# REDRIVERS.net
KiCad netlist of a schematic drawn in Altium Designer
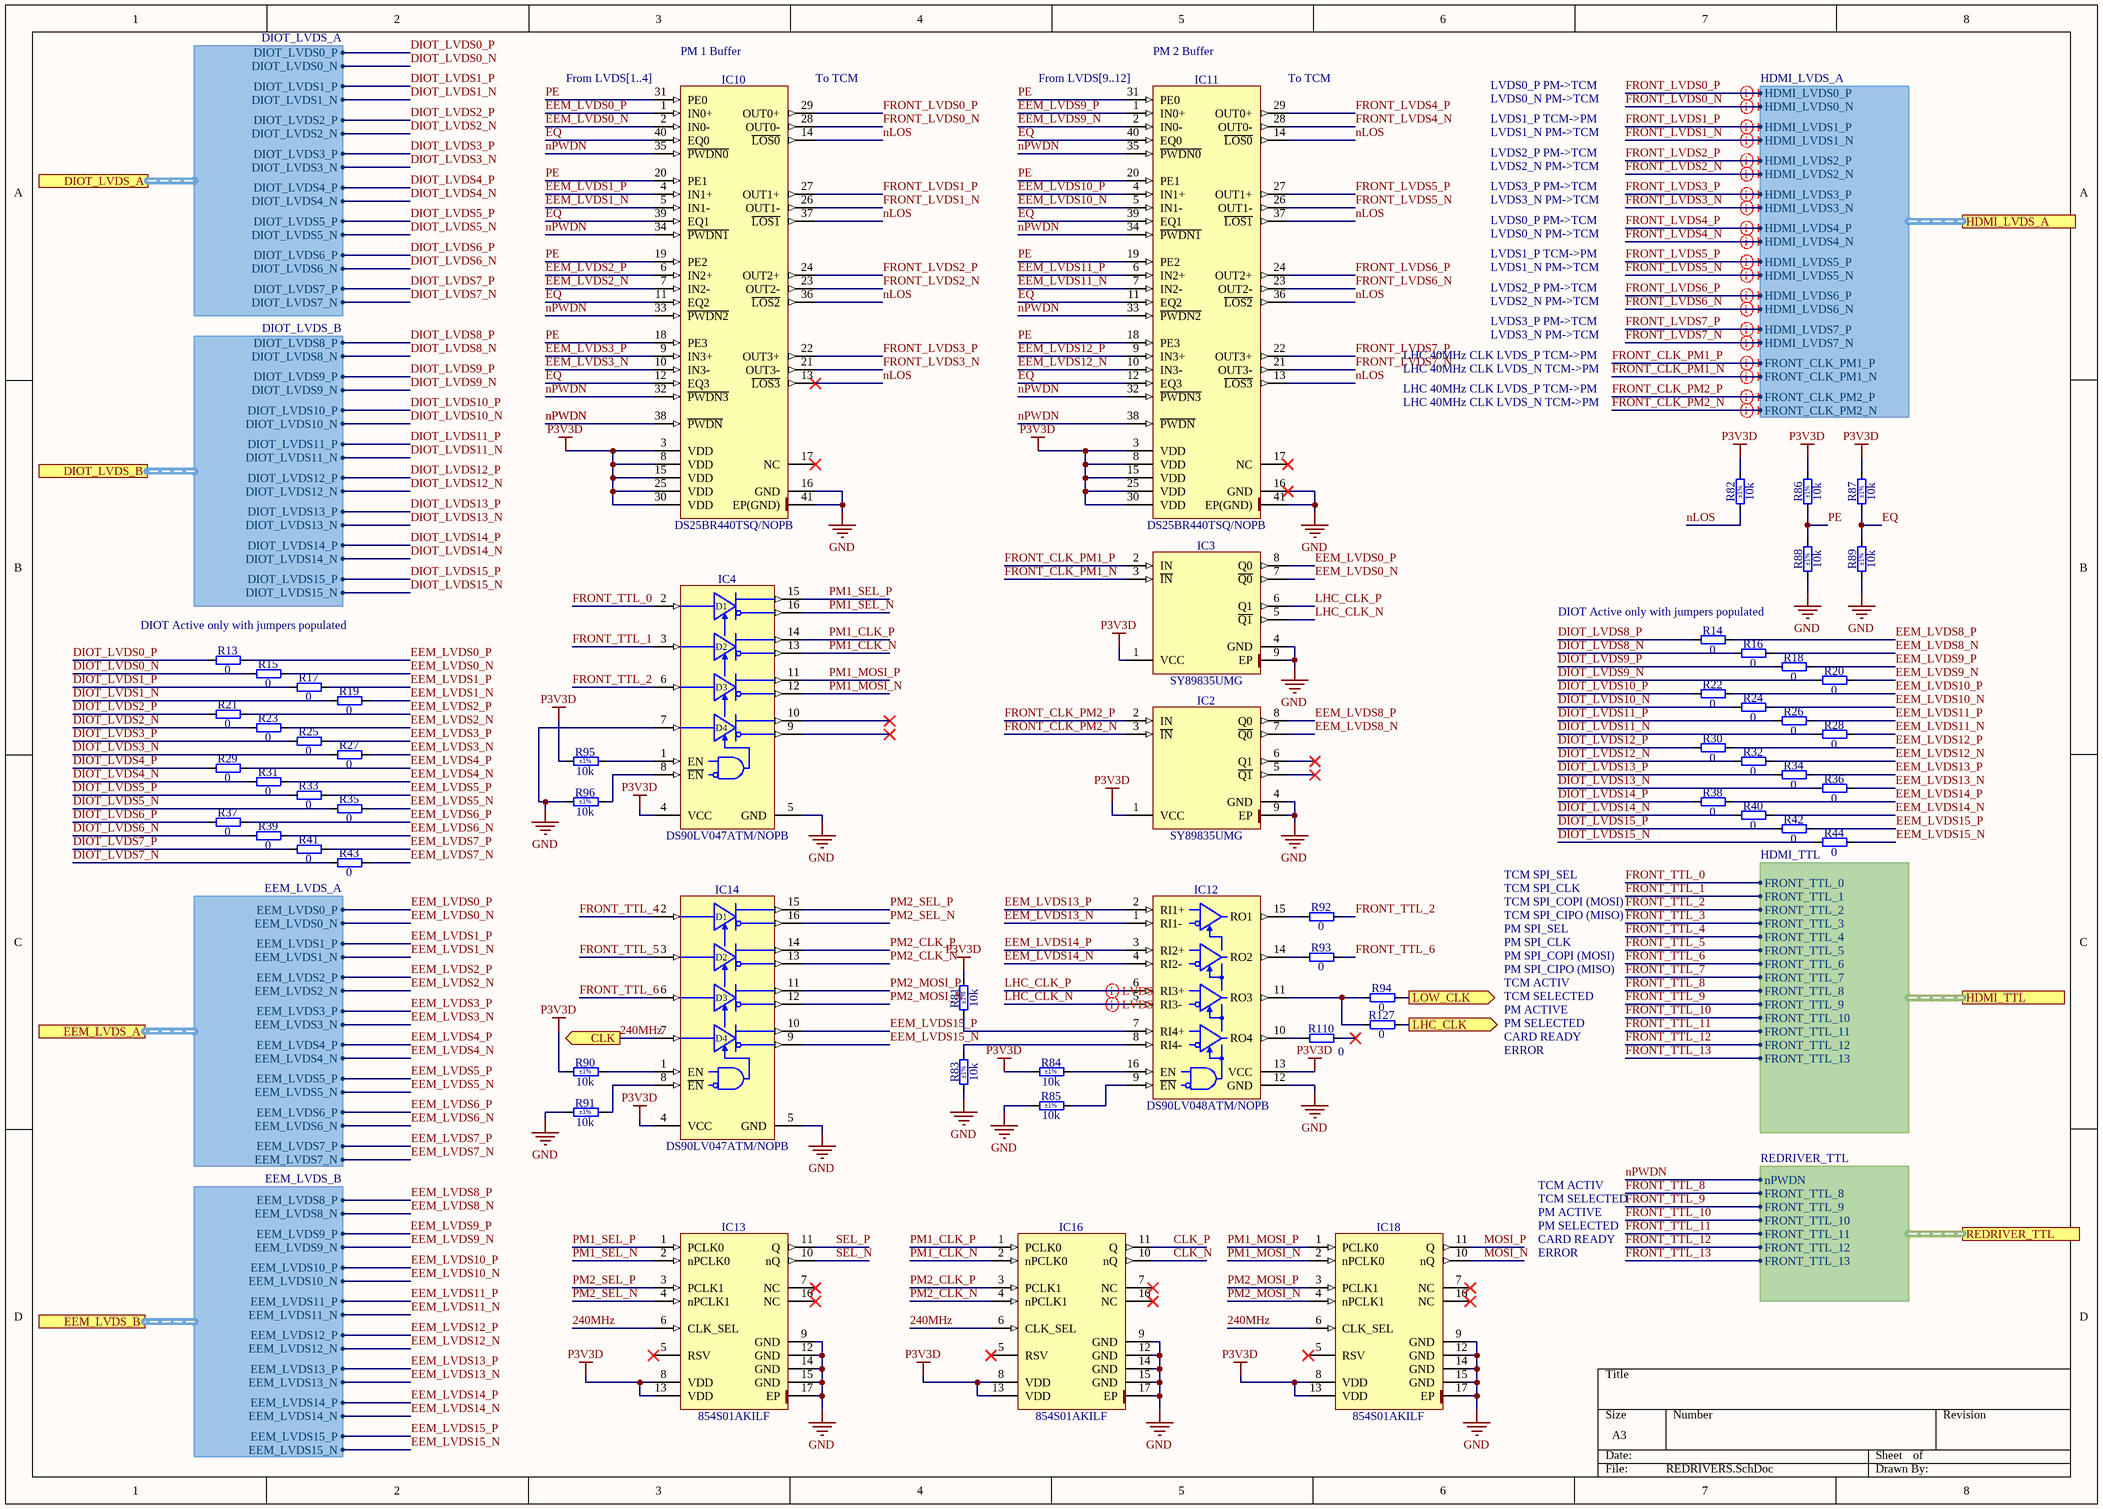
[diagram p0: REDRIVERS.SchDoc]

(export (version "E")
  (design (tool "Eeschema 10.0.6"))
  (components
    (comp (ref "IC2")
      (value "SY89835UMG")
      (footprint "SON50P200X200X90-9N-R70X130")
      (fields (field (name "MANUFACTURER") "MICREL") (field (name "AUTHOR") "CERN DEM MR"))
      (libsource (lib "ICs And Semiconductors") (part "SY89835U"))
    )
    (comp (ref "IC3")
      (value "SY89835UMG")
      (footprint "SON50P200X200X90-9N-R70X130")
      (fields (field (name "MANUFACTURER") "MICREL") (field (name "AUTHOR") "CERN DEM MR"))
      (libsource (lib "ICs And Semiconductors") (part "SY89835U"))
    )
    (comp (ref "IC4")
      (value "DS90LV047ATM/NOPB")
      (footprint "SOIC127P600X175-16N")
      (description "3V LVDS Quad CMOS Differential Line Driver")
      (fields
        (field (name "MANUFACTURER") "TEXAS INSTRUMENTS")
        (field (name "MANUFACTURER PART NUMBER") "DS90LV047ATM")
        (field (name "AUTHOR") "CERN DEM JLC")
      )
      (libsource (lib "ICs And Semiconductors") (part "DS90LV047A"))
    )
    (comp (ref "IC10")
      (value "DS25BR440TSQ/NOPB")
      (footprint "QFN50P600X600X80-41N-S480")
      (description "3.125-Gbps Quad LVDS Buffer with Transmit Pre-Emphasis and Receive Equalization")
      (fields
        (field (name "MANUFACTURER") "TEXAS INSTRUMENTS")
        (field (name "MANUFACTURER PART NUMBER") "DS25BR440TSQ")
        (field (name "AUTHOR") "CERN DEM HF")
      )
      (libsource (lib "ICs And Semiconductors") (part "DS25BR440"))
    )
    (comp (ref "IC11")
      (value "DS25BR440TSQ/NOPB")
      (footprint "QFN50P600X600X80-41N-S480")
      (description "3.125-Gbps Quad LVDS Buffer with Transmit Pre-Emphasis and Receive Equalization")
      (fields
        (field (name "MANUFACTURER") "TEXAS INSTRUMENTS")
        (field (name "MANUFACTURER PART NUMBER") "DS25BR440TSQ")
        (field (name "AUTHOR") "CERN DEM HF")
      )
      (libsource (lib "ICs And Semiconductors") (part "DS25BR440"))
    )
    (comp (ref "IC12")
      (value "DS90LV048ATM/NOPB")
      (footprint "SOIC127P600X175-16N")
      (description "3V LVDS Quad CMOS Differential Line Receiver")
      (fields
        (field (name "MANUFACTURER") "TEXAS INSTRUMENTS")
        (field (name "MANUFACTURER PART NUMBER") "DS90LV048ATM")
        (field (name "AUTHOR") "CERN DEM JLC")
      )
      (libsource (lib "ICs And Semiconductors") (part "DS90LV048A"))
    )
    (comp (ref "IC13")
      (value "854S01AKILF")
      (footprint "QFN50P300X300X100-17N-S180")
      (description "2:1 Differential-to-LVDS Multiplexer")
      (fields
        (field (name "MANUFACTURER") "INTEGRATED DEVICE TECHNOLOGY (IDT)")
        (field (name "AUTHOR") "CERN DEM JLC")
      )
      (libsource (lib "ICs And Semiconductors") (part "854S01AKILF"))
    )
    (comp (ref "IC14")
      (value "DS90LV047ATM/NOPB")
      (footprint "SOIC127P600X175-16N")
      (description "3V LVDS Quad CMOS Differential Line Driver")
      (fields
        (field (name "MANUFACTURER") "TEXAS INSTRUMENTS")
        (field (name "MANUFACTURER PART NUMBER") "DS90LV047ATM")
        (field (name "AUTHOR") "CERN DEM JLC")
      )
      (libsource (lib "ICs And Semiconductors") (part "DS90LV047A"))
    )
    (comp (ref "IC16")
      (value "854S01AKILF")
      (footprint "QFN50P300X300X100-17N-S180")
      (description "2:1 Differential-to-LVDS Multiplexer")
      (fields
        (field (name "MANUFACTURER") "INTEGRATED DEVICE TECHNOLOGY (IDT)")
        (field (name "AUTHOR") "CERN DEM JLC")
      )
      (libsource (lib "ICs And Semiconductors") (part "854S01AKILF"))
    )
    (comp (ref "IC18")
      (value "854S01AKILF")
      (footprint "QFN50P300X300X100-17N-S180")
      (description "2:1 Differential-to-LVDS Multiplexer")
      (fields
        (field (name "MANUFACTURER") "INTEGRATED DEVICE TECHNOLOGY (IDT)")
        (field (name "AUTHOR") "CERN DEM JLC")
      )
      (libsource (lib "ICs And Semiconductors") (part "854S01AKILF"))
    )
    (comp (ref "R13")
      (value "0")
      (footprint "RESC1005X40N")
      (description "Resistor")
      (fields
        (field (name "PART NUMBER") "R0402_0R_JUMPER")
        (field (name "MANUFACTURER") "GENERIC")
        (field (name "AUTHOR") "CERN DEM JLC")
      )
      (libsource (lib "Resistors") (part "Resistor"))
    )
    (comp (ref "R14")
      (value "0")
      (footprint "RESC1005X40N")
      (description "Resistor")
      (fields
        (field (name "PART NUMBER") "R0402_0R_JUMPER")
        (field (name "MANUFACTURER") "GENERIC")
        (field (name "AUTHOR") "CERN DEM JLC")
      )
      (libsource (lib "Resistors") (part "Resistor"))
    )
    (comp (ref "R15")
      (value "0")
      (footprint "RESC1005X40N")
      (description "Resistor")
      (fields
        (field (name "PART NUMBER") "R0402_0R_JUMPER")
        (field (name "MANUFACTURER") "GENERIC")
        (field (name "AUTHOR") "CERN DEM JLC")
      )
      (libsource (lib "Resistors") (part "Resistor"))
    )
    (comp (ref "R16")
      (value "0")
      (footprint "RESC1005X40N")
      (description "Resistor")
      (fields
        (field (name "PART NUMBER") "R0402_0R_JUMPER")
        (field (name "MANUFACTURER") "GENERIC")
        (field (name "AUTHOR") "CERN DEM JLC")
      )
      (libsource (lib "Resistors") (part "Resistor"))
    )
    (comp (ref "R17")
      (value "0")
      (footprint "RESC1005X40N")
      (description "Resistor")
      (fields
        (field (name "PART NUMBER") "R0402_0R_JUMPER")
        (field (name "MANUFACTURER") "GENERIC")
        (field (name "AUTHOR") "CERN DEM JLC")
      )
      (libsource (lib "Resistors") (part "Resistor"))
    )
    (comp (ref "R18")
      (value "0")
      (footprint "RESC1005X40N")
      (description "Resistor")
      (fields
        (field (name "PART NUMBER") "R0402_0R_JUMPER")
        (field (name "MANUFACTURER") "GENERIC")
        (field (name "AUTHOR") "CERN DEM JLC")
      )
      (libsource (lib "Resistors") (part "Resistor"))
    )
    (comp (ref "R19")
      (value "0")
      (footprint "RESC1005X40N")
      (description "Resistor")
      (fields
        (field (name "PART NUMBER") "R0402_0R_JUMPER")
        (field (name "MANUFACTURER") "GENERIC")
        (field (name "AUTHOR") "CERN DEM JLC")
      )
      (libsource (lib "Resistors") (part "Resistor"))
    )
    (comp (ref "R20")
      (value "0")
      (footprint "RESC1005X40N")
      (description "Resistor")
      (fields
        (field (name "PART NUMBER") "R0402_0R_JUMPER")
        (field (name "MANUFACTURER") "GENERIC")
        (field (name "AUTHOR") "CERN DEM JLC")
      )
      (libsource (lib "Resistors") (part "Resistor"))
    )
    (comp (ref "R21")
      (value "0")
      (footprint "RESC1005X40N")
      (description "Resistor")
      (fields
        (field (name "PART NUMBER") "R0402_0R_JUMPER")
        (field (name "MANUFACTURER") "GENERIC")
        (field (name "AUTHOR") "CERN DEM JLC")
      )
      (libsource (lib "Resistors") (part "Resistor"))
    )
    (comp (ref "R22")
      (value "0")
      (footprint "RESC1005X40N")
      (description "Resistor")
      (fields
        (field (name "PART NUMBER") "R0402_0R_JUMPER")
        (field (name "MANUFACTURER") "GENERIC")
        (field (name "AUTHOR") "CERN DEM JLC")
      )
      (libsource (lib "Resistors") (part "Resistor"))
    )
    (comp (ref "R23")
      (value "0")
      (footprint "RESC1005X40N")
      (description "Resistor")
      (fields
        (field (name "PART NUMBER") "R0402_0R_JUMPER")
        (field (name "MANUFACTURER") "GENERIC")
        (field (name "AUTHOR") "CERN DEM JLC")
      )
      (libsource (lib "Resistors") (part "Resistor"))
    )
    (comp (ref "R24")
      (value "0")
      (footprint "RESC1005X40N")
      (description "Resistor")
      (fields
        (field (name "PART NUMBER") "R0402_0R_JUMPER")
        (field (name "MANUFACTURER") "GENERIC")
        (field (name "AUTHOR") "CERN DEM JLC")
      )
      (libsource (lib "Resistors") (part "Resistor"))
    )
    (comp (ref "R25")
      (value "0")
      (footprint "RESC1005X40N")
      (description "Resistor")
      (fields
        (field (name "PART NUMBER") "R0402_0R_JUMPER")
        (field (name "MANUFACTURER") "GENERIC")
        (field (name "AUTHOR") "CERN DEM JLC")
      )
      (libsource (lib "Resistors") (part "Resistor"))
    )
    (comp (ref "R26")
      (value "0")
      (footprint "RESC1005X40N")
      (description "Resistor")
      (fields
        (field (name "PART NUMBER") "R0402_0R_JUMPER")
        (field (name "MANUFACTURER") "GENERIC")
        (field (name "AUTHOR") "CERN DEM JLC")
      )
      (libsource (lib "Resistors") (part "Resistor"))
    )
    (comp (ref "R27")
      (value "0")
      (footprint "RESC1005X40N")
      (description "Resistor")
      (fields
        (field (name "PART NUMBER") "R0402_0R_JUMPER")
        (field (name "MANUFACTURER") "GENERIC")
        (field (name "AUTHOR") "CERN DEM JLC")
      )
      (libsource (lib "Resistors") (part "Resistor"))
    )
    (comp (ref "R28")
      (value "0")
      (footprint "RESC1005X40N")
      (description "Resistor")
      (fields
        (field (name "PART NUMBER") "R0402_0R_JUMPER")
        (field (name "MANUFACTURER") "GENERIC")
        (field (name "AUTHOR") "CERN DEM JLC")
      )
      (libsource (lib "Resistors") (part "Resistor"))
    )
    (comp (ref "R29")
      (value "0")
      (footprint "RESC1005X40N")
      (description "Resistor")
      (fields
        (field (name "PART NUMBER") "R0402_0R_JUMPER")
        (field (name "MANUFACTURER") "GENERIC")
        (field (name "AUTHOR") "CERN DEM JLC")
      )
      (libsource (lib "Resistors") (part "Resistor"))
    )
    (comp (ref "R30")
      (value "0")
      (footprint "RESC1005X40N")
      (description "Resistor")
      (fields
        (field (name "PART NUMBER") "R0402_0R_JUMPER")
        (field (name "MANUFACTURER") "GENERIC")
        (field (name "AUTHOR") "CERN DEM JLC")
      )
      (libsource (lib "Resistors") (part "Resistor"))
    )
    (comp (ref "R31")
      (value "0")
      (footprint "RESC1005X40N")
      (description "Resistor")
      (fields
        (field (name "PART NUMBER") "R0402_0R_JUMPER")
        (field (name "MANUFACTURER") "GENERIC")
        (field (name "AUTHOR") "CERN DEM JLC")
      )
      (libsource (lib "Resistors") (part "Resistor"))
    )
    (comp (ref "R32")
      (value "0")
      (footprint "RESC1005X40N")
      (description "Resistor")
      (fields
        (field (name "PART NUMBER") "R0402_0R_JUMPER")
        (field (name "MANUFACTURER") "GENERIC")
        (field (name "AUTHOR") "CERN DEM JLC")
      )
      (libsource (lib "Resistors") (part "Resistor"))
    )
    (comp (ref "R33")
      (value "0")
      (footprint "RESC1005X40N")
      (description "Resistor")
      (fields
        (field (name "PART NUMBER") "R0402_0R_JUMPER")
        (field (name "MANUFACTURER") "GENERIC")
        (field (name "AUTHOR") "CERN DEM JLC")
      )
      (libsource (lib "Resistors") (part "Resistor"))
    )
    (comp (ref "R34")
      (value "0")
      (footprint "RESC1005X40N")
      (description "Resistor")
      (fields
        (field (name "PART NUMBER") "R0402_0R_JUMPER")
        (field (name "MANUFACTURER") "GENERIC")
        (field (name "AUTHOR") "CERN DEM JLC")
      )
      (libsource (lib "Resistors") (part "Resistor"))
    )
    (comp (ref "R35")
      (value "0")
      (footprint "RESC1005X40N")
      (description "Resistor")
      (fields
        (field (name "PART NUMBER") "R0402_0R_JUMPER")
        (field (name "MANUFACTURER") "GENERIC")
        (field (name "AUTHOR") "CERN DEM JLC")
      )
      (libsource (lib "Resistors") (part "Resistor"))
    )
    (comp (ref "R36")
      (value "0")
      (footprint "RESC1005X40N")
      (description "Resistor")
      (fields
        (field (name "PART NUMBER") "R0402_0R_JUMPER")
        (field (name "MANUFACTURER") "GENERIC")
        (field (name "AUTHOR") "CERN DEM JLC")
      )
      (libsource (lib "Resistors") (part "Resistor"))
    )
    (comp (ref "R37")
      (value "0")
      (footprint "RESC1005X40N")
      (description "Resistor")
      (fields
        (field (name "PART NUMBER") "R0402_0R_JUMPER")
        (field (name "MANUFACTURER") "GENERIC")
        (field (name "AUTHOR") "CERN DEM JLC")
      )
      (libsource (lib "Resistors") (part "Resistor"))
    )
    (comp (ref "R38")
      (value "0")
      (footprint "RESC1005X40N")
      (description "Resistor")
      (fields
        (field (name "PART NUMBER") "R0402_0R_JUMPER")
        (field (name "MANUFACTURER") "GENERIC")
        (field (name "AUTHOR") "CERN DEM JLC")
      )
      (libsource (lib "Resistors") (part "Resistor"))
    )
    (comp (ref "R39")
      (value "0")
      (footprint "RESC1005X40N")
      (description "Resistor")
      (fields
        (field (name "PART NUMBER") "R0402_0R_JUMPER")
        (field (name "MANUFACTURER") "GENERIC")
        (field (name "AUTHOR") "CERN DEM JLC")
      )
      (libsource (lib "Resistors") (part "Resistor"))
    )
    (comp (ref "R40")
      (value "0")
      (footprint "RESC1005X40N")
      (description "Resistor")
      (fields
        (field (name "PART NUMBER") "R0402_0R_JUMPER")
        (field (name "MANUFACTURER") "GENERIC")
        (field (name "AUTHOR") "CERN DEM JLC")
      )
      (libsource (lib "Resistors") (part "Resistor"))
    )
    (comp (ref "R41")
      (value "0")
      (footprint "RESC1005X40N")
      (description "Resistor")
      (fields
        (field (name "PART NUMBER") "R0402_0R_JUMPER")
        (field (name "MANUFACTURER") "GENERIC")
        (field (name "AUTHOR") "CERN DEM JLC")
      )
      (libsource (lib "Resistors") (part "Resistor"))
    )
    (comp (ref "R42")
      (value "0")
      (footprint "RESC1005X40N")
      (description "Resistor")
      (fields
        (field (name "PART NUMBER") "R0402_0R_JUMPER")
        (field (name "MANUFACTURER") "GENERIC")
        (field (name "AUTHOR") "CERN DEM JLC")
      )
      (libsource (lib "Resistors") (part "Resistor"))
    )
    (comp (ref "R43")
      (value "0")
      (footprint "RESC1005X40N")
      (description "Resistor")
      (fields
        (field (name "PART NUMBER") "R0402_0R_JUMPER")
        (field (name "MANUFACTURER") "GENERIC")
        (field (name "AUTHOR") "CERN DEM JLC")
      )
      (libsource (lib "Resistors") (part "Resistor"))
    )
    (comp (ref "R44")
      (value "0")
      (footprint "RESC1005X40N")
      (description "Resistor")
      (fields
        (field (name "PART NUMBER") "R0402_0R_JUMPER")
        (field (name "MANUFACTURER") "GENERIC")
        (field (name "AUTHOR") "CERN DEM JLC")
      )
      (libsource (lib "Resistors") (part "Resistor"))
    )
    (comp (ref "R81")
      (value "10k")
      (footprint "RESC1608X55N")
      (description "Resistor - 1%")
      (fields
        (field (name "TOLERANCE") "±1%")
        (field (name "PART NUMBER") "R0603_10K_1%_0.1W_100PPM")
        (field (name "POWER") "0.1W")
        (field (name "AUTHOR") "CERN DEM JLC")
      )
      (libsource (lib "Resistors") (part "Resistor - 1%"))
    )
    (comp (ref "R82")
      (value "10k")
      (footprint "RESC1608X55N")
      (description "Resistor - 1%")
      (fields
        (field (name "TOLERANCE") "±1%")
        (field (name "PART NUMBER") "R0603_10K_1%_0.1W_100PPM")
        (field (name "POWER") "0.1W")
        (field (name "AUTHOR") "CERN DEM JLC")
      )
      (libsource (lib "Resistors") (part "Resistor - 1%"))
    )
    (comp (ref "R83")
      (value "10k")
      (footprint "RESC1608X55N")
      (description "Resistor - 1%")
      (fields
        (field (name "TOLERANCE") "±1%")
        (field (name "PART NUMBER") "R0603_10K_1%_0.1W_100PPM")
        (field (name "POWER") "0.1W")
        (field (name "AUTHOR") "CERN DEM JLC")
      )
      (libsource (lib "Resistors") (part "Resistor - 1%"))
    )
    (comp (ref "R84")
      (value "10k")
      (footprint "RESC1608X55N")
      (description "Resistor - 1%")
      (fields
        (field (name "TOLERANCE") "±1%")
        (field (name "PART NUMBER") "R0603_10K_1%_0.1W_100PPM")
        (field (name "POWER") "0.1W")
        (field (name "AUTHOR") "CERN DEM JLC")
      )
      (libsource (lib "Resistors") (part "Resistor - 1%"))
    )
    (comp (ref "R85")
      (value "10k")
      (footprint "RESC1608X55N")
      (description "Resistor - 1%")
      (fields
        (field (name "TOLERANCE") "±1%")
        (field (name "PART NUMBER") "R0603_10K_1%_0.1W_100PPM")
        (field (name "POWER") "0.1W")
        (field (name "AUTHOR") "CERN DEM JLC")
      )
      (libsource (lib "Resistors") (part "Resistor - 1%"))
    )
    (comp (ref "R86")
      (value "10k")
      (footprint "RESC1608X55N")
      (description "Resistor - 1%")
      (fields
        (field (name "TOLERANCE") "±1%")
        (field (name "PART NUMBER") "R0603_10K_1%_0.1W_100PPM")
        (field (name "POWER") "0.1W")
        (field (name "AUTHOR") "CERN DEM JLC")
      )
      (libsource (lib "Resistors") (part "Resistor - 1%"))
    )
    (comp (ref "R87")
      (value "10k")
      (footprint "RESC1608X55N")
      (description "Resistor - 1%")
      (fields
        (field (name "TOLERANCE") "±1%")
        (field (name "PART NUMBER") "R0603_10K_1%_0.1W_100PPM")
        (field (name "POWER") "0.1W")
        (field (name "AUTHOR") "CERN DEM JLC")
      )
      (libsource (lib "Resistors") (part "Resistor - 1%"))
    )
    (comp (ref "R88")
      (value "10k")
      (footprint "RESC1608X55N")
      (description "Resistor - 1%")
      (fields
        (field (name "TOLERANCE") "±1%")
        (field (name "PART NUMBER") "R0603_10K_1%_0.1W_100PPM")
        (field (name "POWER") "0.1W")
        (field (name "AUTHOR") "CERN DEM JLC")
      )
      (libsource (lib "Resistors") (part "Resistor - 1%"))
    )
    (comp (ref "R89")
      (value "10k")
      (footprint "RESC1608X55N")
      (description "Resistor - 1%")
      (fields
        (field (name "TOLERANCE") "±1%")
        (field (name "PART NUMBER") "R0603_10K_1%_0.1W_100PPM")
        (field (name "POWER") "0.1W")
        (field (name "AUTHOR") "CERN DEM JLC")
      )
      (libsource (lib "Resistors") (part "Resistor - 1%"))
    )
    (comp (ref "R90")
      (value "10k")
      (footprint "RESC1608X55N")
      (description "Resistor - 1%")
      (fields
        (field (name "TOLERANCE") "±1%")
        (field (name "PART NUMBER") "R0603_10K_1%_0.1W_100PPM")
        (field (name "POWER") "0.1W")
        (field (name "AUTHOR") "CERN DEM JLC")
      )
      (libsource (lib "Resistors") (part "Resistor - 1%"))
    )
    (comp (ref "R91")
      (value "10k")
      (footprint "RESC1608X55N")
      (description "Resistor - 1%")
      (fields
        (field (name "TOLERANCE") "±1%")
        (field (name "PART NUMBER") "R0603_10K_1%_0.1W_100PPM")
        (field (name "POWER") "0.1W")
        (field (name "AUTHOR") "CERN DEM JLC")
      )
      (libsource (lib "Resistors") (part "Resistor - 1%"))
    )
    (comp (ref "R92")
      (value "0")
      (footprint "RESC1005X40N")
      (description "Resistor")
      (fields
        (field (name "PART NUMBER") "R0402_0R_JUMPER")
        (field (name "MANUFACTURER") "GENERIC")
        (field (name "AUTHOR") "CERN DEM JLC")
      )
      (libsource (lib "Resistors") (part "Resistor"))
    )
    (comp (ref "R93")
      (value "0")
      (footprint "RESC1005X40N")
      (description "Resistor")
      (fields
        (field (name "PART NUMBER") "R0402_0R_JUMPER")
        (field (name "MANUFACTURER") "GENERIC")
        (field (name "AUTHOR") "CERN DEM JLC")
      )
      (libsource (lib "Resistors") (part "Resistor"))
    )
    (comp (ref "R94")
      (value "0")
      (footprint "RESC1005X40N")
      (description "Resistor")
      (fields
        (field (name "PART NUMBER") "R0402_0R_JUMPER")
        (field (name "MANUFACTURER") "GENERIC")
        (field (name "AUTHOR") "CERN DEM JLC")
      )
      (libsource (lib "Resistors") (part "Resistor"))
    )
    (comp (ref "R95")
      (value "10k")
      (footprint "RESC1608X55N")
      (description "Resistor - 1%")
      (fields
        (field (name "TOLERANCE") "±1%")
        (field (name "PART NUMBER") "R0603_10K_1%_0.1W_100PPM")
        (field (name "POWER") "0.1W")
        (field (name "AUTHOR") "CERN DEM JLC")
      )
      (libsource (lib "Resistors") (part "Resistor - 1%"))
    )
    (comp (ref "R96")
      (value "10k")
      (footprint "RESC1608X55N")
      (description "Resistor - 1%")
      (fields
        (field (name "TOLERANCE") "±1%")
        (field (name "PART NUMBER") "R0603_10K_1%_0.1W_100PPM")
        (field (name "POWER") "0.1W")
        (field (name "AUTHOR") "CERN DEM JLC")
      )
      (libsource (lib "Resistors") (part "Resistor - 1%"))
    )
    (comp (ref "R110")
      (value "0")
      (footprint "RESC1005X40N")
      (description "Resistor")
      (fields
        (field (name "PART NUMBER") "R0402_0R_JUMPER")
        (field (name "MANUFACTURER") "GENERIC")
        (field (name "AUTHOR") "CERN DEM JLC")
      )
      (libsource (lib "Resistors") (part "Resistor"))
    )
    (comp (ref "R127")
      (value "0")
      (footprint "RESC1005X40N")
      (description "Resistor")
      (fields
        (field (name "PART NUMBER") "R0402_0R_JUMPER")
        (field (name "MANUFACTURER") "GENERIC")
        (field (name "AUTHOR") "CERN DEM JLC")
      )
      (libsource (lib "Resistors") (part "Resistor"))
    )
  )
  (nets
    (net (code "8") (name "/240MHz") (class "Default")
      (node (ref "IC13") (pin "6") (pinfunction "CLK_SEL_6") (pintype "input"))
      (node (ref "IC14") (pin "7") (pinfunction "DIN4_7") (pintype "input"))
      (node (ref "IC16") (pin "6") (pinfunction "CLK_SEL_6") (pintype "input"))
      (node (ref "IC18") (pin "6") (pinfunction "CLK_SEL_6") (pintype "input"))
    )
    (net (code "9") (name "/CLK_N") (class "Default")
      (node (ref "IC16") (pin "10") (pinfunction "nQ_10") (pintype "output"))
    )
    (net (code "10") (name "/CLK_P") (class "Default")
      (node (ref "IC16") (pin "11") (pinfunction "Q_11") (pintype "output"))
    )
    (net (code "11") (name "/DIOT_LVDS0_N") (class "Default")
      (node (ref "R15") (pin "1") (pinfunction "1_1") (pintype "passive"))
    )
    (net (code "12") (name "/DIOT_LVDS0_P") (class "Default")
      (node (ref "R13") (pin "1") (pinfunction "1_1") (pintype "passive"))
    )
    (net (code "13") (name "/DIOT_LVDS1_N") (class "Default")
      (node (ref "R19") (pin "1") (pinfunction "1_1") (pintype "passive"))
    )
    (net (code "14") (name "/DIOT_LVDS1_P") (class "Default")
      (node (ref "R17") (pin "1") (pinfunction "1_1") (pintype "passive"))
    )
    (net (code "15") (name "/DIOT_LVDS2_N") (class "Default")
      (node (ref "R23") (pin "1") (pinfunction "1_1") (pintype "passive"))
    )
    (net (code "16") (name "/DIOT_LVDS2_P") (class "Default")
      (node (ref "R21") (pin "1") (pinfunction "1_1") (pintype "passive"))
    )
    (net (code "17") (name "/DIOT_LVDS3_N") (class "Default")
      (node (ref "R27") (pin "1") (pinfunction "1_1") (pintype "passive"))
    )
    (net (code "18") (name "/DIOT_LVDS3_P") (class "Default")
      (node (ref "R25") (pin "1") (pinfunction "1_1") (pintype "passive"))
    )
    (net (code "19") (name "/DIOT_LVDS4_N") (class "Default")
      (node (ref "R31") (pin "1") (pinfunction "1_1") (pintype "passive"))
    )
    (net (code "20") (name "/DIOT_LVDS4_P") (class "Default")
      (node (ref "R29") (pin "1") (pinfunction "1_1") (pintype "passive"))
    )
    (net (code "21") (name "/DIOT_LVDS5_N") (class "Default")
      (node (ref "R35") (pin "1") (pinfunction "1_1") (pintype "passive"))
    )
    (net (code "22") (name "/DIOT_LVDS5_P") (class "Default")
      (node (ref "R33") (pin "1") (pinfunction "1_1") (pintype "passive"))
    )
    (net (code "23") (name "/DIOT_LVDS6_N") (class "Default")
      (node (ref "R39") (pin "1") (pinfunction "1_1") (pintype "passive"))
    )
    (net (code "24") (name "/DIOT_LVDS6_P") (class "Default")
      (node (ref "R37") (pin "1") (pinfunction "1_1") (pintype "passive"))
    )
    (net (code "25") (name "/DIOT_LVDS7_N") (class "Default")
      (node (ref "R43") (pin "1") (pinfunction "1_1") (pintype "passive"))
    )
    (net (code "26") (name "/DIOT_LVDS7_P") (class "Default")
      (node (ref "R41") (pin "1") (pinfunction "1_1") (pintype "passive"))
    )
    (net (code "27") (name "/DIOT_LVDS8_N") (class "Default")
      (node (ref "R16") (pin "1") (pinfunction "1_1") (pintype "passive"))
    )
    (net (code "28") (name "/DIOT_LVDS8_P") (class "Default")
      (node (ref "R14") (pin "1") (pinfunction "1_1") (pintype "passive"))
    )
    (net (code "29") (name "/DIOT_LVDS9_N") (class "Default")
      (node (ref "R20") (pin "1") (pinfunction "1_1") (pintype "passive"))
    )
    (net (code "30") (name "/DIOT_LVDS9_P") (class "Default")
      (node (ref "R18") (pin "1") (pinfunction "1_1") (pintype "passive"))
    )
    (net (code "31") (name "/DIOT_LVDS10_N") (class "Default")
      (node (ref "R24") (pin "1") (pinfunction "1_1") (pintype "passive"))
    )
    (net (code "32") (name "/DIOT_LVDS10_P") (class "Default")
      (node (ref "R22") (pin "1") (pinfunction "1_1") (pintype "passive"))
    )
    (net (code "33") (name "/DIOT_LVDS11_N") (class "Default")
      (node (ref "R28") (pin "1") (pinfunction "1_1") (pintype "passive"))
    )
    (net (code "34") (name "/DIOT_LVDS11_P") (class "Default")
      (node (ref "R26") (pin "1") (pinfunction "1_1") (pintype "passive"))
    )
    (net (code "35") (name "/DIOT_LVDS12_N") (class "Default")
      (node (ref "R32") (pin "1") (pinfunction "1_1") (pintype "passive"))
    )
    (net (code "36") (name "/DIOT_LVDS12_P") (class "Default")
      (node (ref "R30") (pin "1") (pinfunction "1_1") (pintype "passive"))
    )
    (net (code "37") (name "/DIOT_LVDS13_N") (class "Default")
      (node (ref "R36") (pin "1") (pinfunction "1_1") (pintype "passive"))
    )
    (net (code "38") (name "/DIOT_LVDS13_P") (class "Default")
      (node (ref "R34") (pin "1") (pinfunction "1_1") (pintype "passive"))
    )
    (net (code "39") (name "/DIOT_LVDS14_N") (class "Default")
      (node (ref "R40") (pin "1") (pinfunction "1_1") (pintype "passive"))
    )
    (net (code "40") (name "/DIOT_LVDS14_P") (class "Default")
      (node (ref "R38") (pin "1") (pinfunction "1_1") (pintype "passive"))
    )
    (net (code "41") (name "/DIOT_LVDS15_N") (class "Default")
      (node (ref "R44") (pin "1") (pinfunction "1_1") (pintype "passive"))
    )
    (net (code "42") (name "/DIOT_LVDS15_P") (class "Default")
      (node (ref "R42") (pin "1") (pinfunction "1_1") (pintype "passive"))
    )
    (net (code "43") (name "/EEM_LVDS0_N") (class "Default")
      (node (ref "IC10") (pin "2") (pinfunction "IN0-_2") (pintype "input"))
      (node (ref "IC3") (pin "7") (pinfunction "~{Q0}_7") (pintype "output"))
      (node (ref "R15") (pin "2") (pinfunction "2_2") (pintype "passive"))
    )
    (net (code "44") (name "/EEM_LVDS0_P") (class "Default")
      (node (ref "IC10") (pin "1") (pinfunction "IN0+_1") (pintype "input"))
      (node (ref "IC3") (pin "8") (pinfunction "Q0_8") (pintype "output"))
      (node (ref "R13") (pin "2") (pinfunction "2_2") (pintype "passive"))
    )
    (net (code "45") (name "/EEM_LVDS1_N") (class "Default")
      (node (ref "IC10") (pin "5") (pinfunction "IN1-_5") (pintype "input"))
      (node (ref "R19") (pin "2") (pinfunction "2_2") (pintype "passive"))
    )
    (net (code "46") (name "/EEM_LVDS1_P") (class "Default")
      (node (ref "IC10") (pin "4") (pinfunction "IN1+_4") (pintype "input"))
      (node (ref "R17") (pin "2") (pinfunction "2_2") (pintype "passive"))
    )
    (net (code "47") (name "/EEM_LVDS2_N") (class "Default")
      (node (ref "IC10") (pin "7") (pinfunction "IN2-_7") (pintype "input"))
      (node (ref "R23") (pin "2") (pinfunction "2_2") (pintype "passive"))
    )
    (net (code "48") (name "/EEM_LVDS2_P") (class "Default")
      (node (ref "IC10") (pin "6") (pinfunction "IN2+_6") (pintype "input"))
      (node (ref "R21") (pin "2") (pinfunction "2_2") (pintype "passive"))
    )
    (net (code "49") (name "/EEM_LVDS3_N") (class "Default")
      (node (ref "IC10") (pin "10") (pinfunction "IN3-_10") (pintype "input"))
      (node (ref "R27") (pin "2") (pinfunction "2_2") (pintype "passive"))
    )
    (net (code "50") (name "/EEM_LVDS3_P") (class "Default")
      (node (ref "IC10") (pin "9") (pinfunction "IN3+_9") (pintype "input"))
      (node (ref "R25") (pin "2") (pinfunction "2_2") (pintype "passive"))
    )
    (net (code "51") (name "/EEM_LVDS4_N") (class "Default")
      (node (ref "R31") (pin "2") (pinfunction "2_2") (pintype "passive"))
    )
    (net (code "52") (name "/EEM_LVDS4_P") (class "Default")
      (node (ref "R29") (pin "2") (pinfunction "2_2") (pintype "passive"))
    )
    (net (code "53") (name "/EEM_LVDS5_N") (class "Default")
      (node (ref "R35") (pin "2") (pinfunction "2_2") (pintype "passive"))
    )
    (net (code "54") (name "/EEM_LVDS5_P") (class "Default")
      (node (ref "R33") (pin "2") (pinfunction "2_2") (pintype "passive"))
    )
    (net (code "55") (name "/EEM_LVDS6_N") (class "Default")
      (node (ref "R39") (pin "2") (pinfunction "2_2") (pintype "passive"))
    )
    (net (code "56") (name "/EEM_LVDS6_P") (class "Default")
      (node (ref "R37") (pin "2") (pinfunction "2_2") (pintype "passive"))
    )
    (net (code "57") (name "/EEM_LVDS7_N") (class "Default")
      (node (ref "R43") (pin "2") (pinfunction "2_2") (pintype "passive"))
    )
    (net (code "58") (name "/EEM_LVDS7_P") (class "Default")
      (node (ref "R41") (pin "2") (pinfunction "2_2") (pintype "passive"))
    )
    (net (code "59") (name "/EEM_LVDS8_N") (class "Default")
      (node (ref "IC2") (pin "7") (pinfunction "~{Q0}_7") (pintype "output"))
      (node (ref "R16") (pin "2") (pinfunction "2_2") (pintype "passive"))
    )
    (net (code "60") (name "/EEM_LVDS8_P") (class "Default")
      (node (ref "IC2") (pin "8") (pinfunction "Q0_8") (pintype "output"))
      (node (ref "R14") (pin "2") (pinfunction "2_2") (pintype "passive"))
    )
    (net (code "61") (name "/EEM_LVDS9_N") (class "Default")
      (node (ref "IC11") (pin "2") (pinfunction "IN0-_2") (pintype "input"))
      (node (ref "R20") (pin "2") (pinfunction "2_2") (pintype "passive"))
    )
    (net (code "62") (name "/EEM_LVDS9_P") (class "Default")
      (node (ref "IC11") (pin "1") (pinfunction "IN0+_1") (pintype "input"))
      (node (ref "R18") (pin "2") (pinfunction "2_2") (pintype "passive"))
    )
    (net (code "63") (name "/EEM_LVDS10_N") (class "Default")
      (node (ref "IC11") (pin "5") (pinfunction "IN1-_5") (pintype "input"))
      (node (ref "R24") (pin "2") (pinfunction "2_2") (pintype "passive"))
    )
    (net (code "64") (name "/EEM_LVDS10_P") (class "Default")
      (node (ref "IC11") (pin "4") (pinfunction "IN1+_4") (pintype "input"))
      (node (ref "R22") (pin "2") (pinfunction "2_2") (pintype "passive"))
    )
    (net (code "65") (name "/EEM_LVDS11_N") (class "Default")
      (node (ref "IC11") (pin "7") (pinfunction "IN2-_7") (pintype "input"))
      (node (ref "R28") (pin "2") (pinfunction "2_2") (pintype "passive"))
    )
    (net (code "66") (name "/EEM_LVDS11_P") (class "Default")
      (node (ref "IC11") (pin "6") (pinfunction "IN2+_6") (pintype "input"))
      (node (ref "R26") (pin "2") (pinfunction "2_2") (pintype "passive"))
    )
    (net (code "67") (name "/EEM_LVDS12_N") (class "Default")
      (node (ref "IC11") (pin "10") (pinfunction "IN3-_10") (pintype "input"))
      (node (ref "R32") (pin "2") (pinfunction "2_2") (pintype "passive"))
    )
    (net (code "68") (name "/EEM_LVDS12_P") (class "Default")
      (node (ref "IC11") (pin "9") (pinfunction "IN3+_9") (pintype "input"))
      (node (ref "R30") (pin "2") (pinfunction "2_2") (pintype "passive"))
    )
    (net (code "69") (name "/EEM_LVDS13_N") (class "Default")
      (node (ref "IC12") (pin "1") (pinfunction "RI1-_1") (pintype "input"))
      (node (ref "R36") (pin "2") (pinfunction "2_2") (pintype "passive"))
    )
    (net (code "70") (name "/EEM_LVDS13_P") (class "Default")
      (node (ref "IC12") (pin "2") (pinfunction "RI1+_2") (pintype "input"))
      (node (ref "R34") (pin "2") (pinfunction "2_2") (pintype "passive"))
    )
    (net (code "71") (name "/EEM_LVDS14_N") (class "Default")
      (node (ref "IC12") (pin "4") (pinfunction "RI2-_4") (pintype "input"))
      (node (ref "R40") (pin "2") (pinfunction "2_2") (pintype "passive"))
    )
    (net (code "72") (name "/EEM_LVDS14_P") (class "Default")
      (node (ref "IC12") (pin "3") (pinfunction "RI2+_3") (pintype "input"))
      (node (ref "R38") (pin "2") (pinfunction "2_2") (pintype "passive"))
    )
    (net (code "73") (name "/EEM_LVDS15_N") (class "Default")
      (node (ref "IC14") (pin "9") (pinfunction "DOUT4-_9") (pintype "output"))
      (node (ref "R44") (pin "2") (pinfunction "2_2") (pintype "passive"))
    )
    (net (code "74") (name "/EEM_LVDS15_P") (class "Default")
      (node (ref "IC14") (pin "10") (pinfunction "DOUT4+_10") (pintype "output"))
      (node (ref "R42") (pin "2") (pinfunction "2_2") (pintype "passive"))
    )
    (net (code "75") (name "/EQ") (class "Default")
      (node (ref "IC10") (pin "11") (pinfunction "EQ2_11") (pintype "input"))
      (node (ref "IC10") (pin "12") (pinfunction "EQ3_12") (pintype "input"))
      (node (ref "IC10") (pin "39") (pinfunction "EQ1_39") (pintype "input"))
      (node (ref "IC10") (pin "40") (pinfunction "EQ0_40") (pintype "input"))
      (node (ref "IC11") (pin "11") (pinfunction "EQ2_11") (pintype "input"))
      (node (ref "IC11") (pin "12") (pinfunction "EQ3_12") (pintype "input"))
      (node (ref "IC11") (pin "39") (pinfunction "EQ1_39") (pintype "input"))
      (node (ref "IC11") (pin "40") (pinfunction "EQ0_40") (pintype "input"))
      (node (ref "R87") (pin "1") (pinfunction "1_1") (pintype "passive"))
      (node (ref "R89") (pin "2") (pinfunction "2_2") (pintype "passive"))
    )
    (net (code "76") (name "/FRONT_CLK_PM1_N") (class "Default")
      (node (ref "IC3") (pin "3") (pinfunction "~{IN}_3") (pintype "input"))
    )
    (net (code "77") (name "/FRONT_CLK_PM1_P") (class "Default")
      (node (ref "IC3") (pin "2") (pinfunction "IN_2") (pintype "input"))
    )
    (net (code "78") (name "/FRONT_CLK_PM2_N") (class "Default")
      (node (ref "IC2") (pin "3") (pinfunction "~{IN}_3") (pintype "input"))
    )
    (net (code "79") (name "/FRONT_CLK_PM2_P") (class "Default")
      (node (ref "IC2") (pin "2") (pinfunction "IN_2") (pintype "input"))
    )
    (net (code "80") (name "/FRONT_LVDS0_N") (class "Default")
      (node (ref "IC10") (pin "28") (pinfunction "OUT0-_28") (pintype "output"))
    )
    (net (code "81") (name "/FRONT_LVDS0_P") (class "Default")
      (node (ref "IC10") (pin "29") (pinfunction "OUT0+_29") (pintype "output"))
    )
    (net (code "82") (name "/FRONT_LVDS1_N") (class "Default")
      (node (ref "IC10") (pin "26") (pinfunction "OUT1-_26") (pintype "output"))
    )
    (net (code "83") (name "/FRONT_LVDS1_P") (class "Default")
      (node (ref "IC10") (pin "27") (pinfunction "OUT1+_27") (pintype "output"))
    )
    (net (code "84") (name "/FRONT_LVDS2_N") (class "Default")
      (node (ref "IC10") (pin "23") (pinfunction "OUT2-_23") (pintype "output"))
    )
    (net (code "85") (name "/FRONT_LVDS2_P") (class "Default")
      (node (ref "IC10") (pin "24") (pinfunction "OUT2+_24") (pintype "output"))
    )
    (net (code "86") (name "/FRONT_LVDS3_N") (class "Default")
      (node (ref "IC10") (pin "21") (pinfunction "OUT3-_21") (pintype "output"))
    )
    (net (code "87") (name "/FRONT_LVDS3_P") (class "Default")
      (node (ref "IC10") (pin "22") (pinfunction "OUT3+_22") (pintype "output"))
    )
    (net (code "88") (name "/FRONT_LVDS4_N") (class "Default")
      (node (ref "IC11") (pin "28") (pinfunction "OUT0-_28") (pintype "output"))
    )
    (net (code "89") (name "/FRONT_LVDS4_P") (class "Default")
      (node (ref "IC11") (pin "29") (pinfunction "OUT0+_29") (pintype "output"))
    )
    (net (code "90") (name "/FRONT_LVDS5_N") (class "Default")
      (node (ref "IC11") (pin "26") (pinfunction "OUT1-_26") (pintype "output"))
    )
    (net (code "91") (name "/FRONT_LVDS5_P") (class "Default")
      (node (ref "IC11") (pin "27") (pinfunction "OUT1+_27") (pintype "output"))
    )
    (net (code "92") (name "/FRONT_LVDS6_N") (class "Default")
      (node (ref "IC11") (pin "23") (pinfunction "OUT2-_23") (pintype "output"))
    )
    (net (code "93") (name "/FRONT_LVDS6_P") (class "Default")
      (node (ref "IC11") (pin "24") (pinfunction "OUT2+_24") (pintype "output"))
    )
    (net (code "94") (name "/FRONT_LVDS7_N") (class "Default")
      (node (ref "IC11") (pin "21") (pinfunction "OUT3-_21") (pintype "output"))
    )
    (net (code "95") (name "/FRONT_LVDS7_P") (class "Default")
      (node (ref "IC11") (pin "22") (pinfunction "OUT3+_22") (pintype "output"))
    )
    (net (code "96") (name "/FRONT_TTL_0") (class "Default")
      (node (ref "IC4") (pin "2") (pinfunction "DIN1_2") (pintype "input"))
    )
    (net (code "97") (name "/FRONT_TTL_1") (class "Default")
      (node (ref "IC4") (pin "3") (pinfunction "DIN2_3") (pintype "input"))
    )
    (net (code "98") (name "/FRONT_TTL_2") (class "Default")
      (node (ref "IC4") (pin "6") (pinfunction "DIN3_6") (pintype "input"))
      (node (ref "R92") (pin "2") (pinfunction "2_2") (pintype "passive"))
    )
    (net (code "100") (name "/FRONT_TTL_4") (class "Default")
      (node (ref "IC14") (pin "2") (pinfunction "DIN1_2") (pintype "input"))
    )
    (net (code "101") (name "/FRONT_TTL_5") (class "Default")
      (node (ref "IC14") (pin "3") (pinfunction "DIN2_3") (pintype "input"))
    )
    (net (code "102") (name "/FRONT_TTL_6") (class "Default")
      (node (ref "IC14") (pin "6") (pinfunction "DIN3_6") (pintype "input"))
      (node (ref "R93") (pin "2") (pinfunction "2_2") (pintype "passive"))
    )
    (net (code "110") (name "/LHC_CLK") (class "Default")
      (node (ref "R127") (pin "2") (pinfunction "2_2") (pintype "passive"))
    )
    (net (code "111") (name "/LHC_CLK_N") (class "Default")
      (node (ref "IC12") (pin "5") (pinfunction "RI3-_5") (pintype "input"))
      (node (ref "IC3") (pin "5") (pinfunction "~{Q1}_5") (pintype "output"))
    )
    (net (code "112") (name "/LHC_CLK_P") (class "Default")
      (node (ref "IC12") (pin "6") (pinfunction "RI3+_6") (pintype "input"))
      (node (ref "IC3") (pin "6") (pinfunction "Q1_6") (pintype "output"))
    )
    (net (code "113") (name "/LOW_CLK") (class "Default")
      (node (ref "R94") (pin "2") (pinfunction "2_2") (pintype "passive"))
    )
    (net (code "114") (name "/MOSI_N") (class "Default")
      (node (ref "IC18") (pin "10") (pinfunction "nQ_10") (pintype "output"))
    )
    (net (code "115") (name "/MOSI_P") (class "Default")
      (node (ref "IC18") (pin "11") (pinfunction "Q_11") (pintype "output"))
    )
    (net (code "116") (name "/PE") (class "Default")
      (node (ref "IC10") (pin "18") (pinfunction "PE3_18") (pintype "input"))
      (node (ref "IC10") (pin "19") (pinfunction "PE2_19") (pintype "input"))
      (node (ref "IC10") (pin "20") (pinfunction "PE1_20") (pintype "input"))
      (node (ref "IC10") (pin "31") (pinfunction "PE0_31") (pintype "input"))
      (node (ref "IC11") (pin "18") (pinfunction "PE3_18") (pintype "input"))
      (node (ref "IC11") (pin "19") (pinfunction "PE2_19") (pintype "input"))
      (node (ref "IC11") (pin "20") (pinfunction "PE1_20") (pintype "input"))
      (node (ref "IC11") (pin "31") (pinfunction "PE0_31") (pintype "input"))
      (node (ref "R86") (pin "1") (pinfunction "1_1") (pintype "passive"))
      (node (ref "R88") (pin "2") (pinfunction "2_2") (pintype "passive"))
    )
    (net (code "117") (name "/PM1_CLK_N") (class "Default")
      (node (ref "IC16") (pin "2") (pinfunction "nPCLK0_2") (pintype "input"))
      (node (ref "IC4") (pin "13") (pinfunction "DOUT2-_13") (pintype "output"))
    )
    (net (code "118") (name "/PM1_CLK_P") (class "Default")
      (node (ref "IC16") (pin "1") (pinfunction "PCLK0_1") (pintype "input"))
      (node (ref "IC4") (pin "14") (pinfunction "DOUT2+_14") (pintype "output"))
    )
    (net (code "119") (name "/PM1_MOSI_N") (class "Default")
      (node (ref "IC18") (pin "2") (pinfunction "nPCLK0_2") (pintype "input"))
      (node (ref "IC4") (pin "12") (pinfunction "DOUT3-_12") (pintype "output"))
    )
    (net (code "120") (name "/PM1_MOSI_P") (class "Default")
      (node (ref "IC18") (pin "1") (pinfunction "PCLK0_1") (pintype "input"))
      (node (ref "IC4") (pin "11") (pinfunction "DOUT3+_11") (pintype "output"))
    )
    (net (code "121") (name "/PM1_SEL_N") (class "Default")
      (node (ref "IC13") (pin "2") (pinfunction "nPCLK0_2") (pintype "input"))
      (node (ref "IC4") (pin "16") (pinfunction "DOUT1-_16") (pintype "output"))
    )
    (net (code "122") (name "/PM1_SEL_P") (class "Default")
      (node (ref "IC13") (pin "1") (pinfunction "PCLK0_1") (pintype "input"))
      (node (ref "IC4") (pin "15") (pinfunction "DOUT1+_15") (pintype "output"))
    )
    (net (code "123") (name "/PM2_CLK_N") (class "Default")
      (node (ref "IC14") (pin "13") (pinfunction "DOUT2-_13") (pintype "output"))
      (node (ref "IC16") (pin "4") (pinfunction "nPCLK1_4") (pintype "input"))
    )
    (net (code "124") (name "/PM2_CLK_P") (class "Default")
      (node (ref "IC14") (pin "14") (pinfunction "DOUT2+_14") (pintype "output"))
      (node (ref "IC16") (pin "3") (pinfunction "PCLK1_3") (pintype "input"))
    )
    (net (code "125") (name "/PM2_MOSI_N") (class "Default")
      (node (ref "IC14") (pin "12") (pinfunction "DOUT3-_12") (pintype "output"))
      (node (ref "IC18") (pin "4") (pinfunction "nPCLK1_4") (pintype "input"))
    )
    (net (code "126") (name "/PM2_MOSI_P") (class "Default")
      (node (ref "IC14") (pin "11") (pinfunction "DOUT3+_11") (pintype "output"))
      (node (ref "IC18") (pin "3") (pinfunction "PCLK1_3") (pintype "input"))
    )
    (net (code "127") (name "/PM2_SEL_N") (class "Default")
      (node (ref "IC13") (pin "4") (pinfunction "nPCLK1_4") (pintype "input"))
      (node (ref "IC14") (pin "16") (pinfunction "DOUT1-_16") (pintype "output"))
    )
    (net (code "128") (name "/PM2_SEL_P") (class "Default")
      (node (ref "IC13") (pin "3") (pinfunction "PCLK1_3") (pintype "input"))
      (node (ref "IC14") (pin "15") (pinfunction "DOUT1+_15") (pintype "output"))
    )
    (net (code "129") (name "/SEL_N") (class "Default")
      (node (ref "IC13") (pin "10") (pinfunction "nQ_10") (pintype "output"))
    )
    (net (code "130") (name "/SEL_P") (class "Default")
      (node (ref "IC13") (pin "11") (pinfunction "Q_11") (pintype "output"))
    )
    (net (code "131") (name "/nLOS") (class "Default")
      (node (ref "IC10") (pin "13") (pinfunction "~{LOS3}_13") (pintype "output"))
      (node (ref "IC10") (pin "14") (pinfunction "~{LOS0}_14") (pintype "output"))
      (node (ref "IC10") (pin "36") (pinfunction "~{LOS2}_36") (pintype "output"))
      (node (ref "IC10") (pin "37") (pinfunction "~{LOS1}_37") (pintype "output"))
      (node (ref "IC11") (pin "13") (pinfunction "~{LOS3}_13") (pintype "output"))
      (node (ref "IC11") (pin "14") (pinfunction "~{LOS0}_14") (pintype "output"))
      (node (ref "IC11") (pin "36") (pinfunction "~{LOS2}_36") (pintype "output"))
      (node (ref "IC11") (pin "37") (pinfunction "~{LOS1}_37") (pintype "output"))
      (node (ref "R82") (pin "1") (pinfunction "1_1") (pintype "passive"))
    )
    (net (code "132") (name "/nPWDN") (class "Default")
      (node (ref "IC10") (pin "32") (pinfunction "~{PWDN3}_32") (pintype "input"))
      (node (ref "IC10") (pin "33") (pinfunction "~{PWDN2}_33") (pintype "input"))
      (node (ref "IC10") (pin "34") (pinfunction "~{PWDN1}_34") (pintype "input"))
      (node (ref "IC10") (pin "35") (pinfunction "~{PWDN0}_35") (pintype "input"))
      (node (ref "IC10") (pin "38") (pinfunction "~{PWDN}_38") (pintype "input"))
      (node (ref "IC11") (pin "32") (pinfunction "~{PWDN3}_32") (pintype "input"))
      (node (ref "IC11") (pin "33") (pinfunction "~{PWDN2}_33") (pintype "input"))
      (node (ref "IC11") (pin "34") (pinfunction "~{PWDN1}_34") (pintype "input"))
      (node (ref "IC11") (pin "35") (pinfunction "~{PWDN0}_35") (pintype "input"))
      (node (ref "IC11") (pin "38") (pinfunction "~{PWDN}_38") (pintype "input"))
    )
    (net (code "140") (name "GND") (class "Default")
      (node (ref "IC10") (pin "16") (pinfunction "GND_16") (pintype "power_in"))
      (node (ref "IC10") (pin "41") (pinfunction "EP(GND)_41") (pintype "power_in"))
      (node (ref "IC11") (pin "16") (pinfunction "GND_16") (pintype "power_in"))
      (node (ref "IC11") (pin "41") (pinfunction "EP(GND)_41") (pintype "power_in"))
      (node (ref "IC12") (pin "12") (pinfunction "GND_12") (pintype "power_in"))
      (node (ref "IC13") (pin "12") (pinfunction "GND_12") (pintype "power_in"))
      (node (ref "IC13") (pin "14") (pinfunction "GND_14") (pintype "power_in"))
      (node (ref "IC13") (pin "15") (pinfunction "GND_15") (pintype "power_in"))
      (node (ref "IC13") (pin "17") (pinfunction "EP_17") (pintype "power_in"))
      (node (ref "IC13") (pin "9") (pinfunction "GND_9") (pintype "power_in"))
      (node (ref "IC14") (pin "5") (pinfunction "GND_5") (pintype "power_in"))
      (node (ref "IC16") (pin "12") (pinfunction "GND_12") (pintype "power_in"))
      (node (ref "IC16") (pin "14") (pinfunction "GND_14") (pintype "power_in"))
      (node (ref "IC16") (pin "15") (pinfunction "GND_15") (pintype "power_in"))
      (node (ref "IC16") (pin "17") (pinfunction "EP_17") (pintype "power_in"))
      (node (ref "IC16") (pin "9") (pinfunction "GND_9") (pintype "power_in"))
      (node (ref "IC18") (pin "12") (pinfunction "GND_12") (pintype "power_in"))
      (node (ref "IC18") (pin "14") (pinfunction "GND_14") (pintype "power_in"))
      (node (ref "IC18") (pin "15") (pinfunction "GND_15") (pintype "power_in"))
      (node (ref "IC18") (pin "17") (pinfunction "EP_17") (pintype "power_in"))
      (node (ref "IC18") (pin "9") (pinfunction "GND_9") (pintype "power_in"))
      (node (ref "IC2") (pin "4") (pinfunction "GND_4") (pintype "power_in"))
      (node (ref "IC2") (pin "9") (pinfunction "EP_9") (pintype "power_in"))
      (node (ref "IC3") (pin "4") (pinfunction "GND_4") (pintype "power_in"))
      (node (ref "IC3") (pin "9") (pinfunction "EP_9") (pintype "power_in"))
      (node (ref "IC4") (pin "5") (pinfunction "GND_5") (pintype "power_in"))
      (node (ref "IC4") (pin "7") (pinfunction "DIN4_7") (pintype "input"))
      (node (ref "R83") (pin "1") (pinfunction "1_1") (pintype "passive"))
      (node (ref "R85") (pin "1") (pinfunction "1_1") (pintype "passive"))
      (node (ref "R88") (pin "1") (pinfunction "1_1") (pintype "passive"))
      (node (ref "R89") (pin "1") (pinfunction "1_1") (pintype "passive"))
      (node (ref "R91") (pin "2") (pinfunction "2_2") (pintype "passive"))
      (node (ref "R96") (pin "2") (pinfunction "2_2") (pintype "passive"))
    )
    (net (code "141") (name "Net-(IC4-EN)") (class "Default")
      (node (ref "IC4") (pin "1") (pinfunction "EN_1") (pintype "input"))
      (node (ref "R95") (pin "1") (pinfunction "1_1") (pintype "passive"))
    )
    (net (code "142") (name "Net-(IC4-~{EN})") (class "Default")
      (node (ref "IC4") (pin "8") (pinfunction "~{EN}_8") (pintype "input"))
      (node (ref "R96") (pin "1") (pinfunction "1_1") (pintype "passive"))
    )
    (net (code "143") (name "Net-(IC12-EN)") (class "Default")
      (node (ref "IC12") (pin "16") (pinfunction "EN_16") (pintype "input"))
      (node (ref "R84") (pin "2") (pinfunction "2_2") (pintype "passive"))
    )
    (net (code "144") (name "Net-(IC12-RI4+)") (class "Default")
      (node (ref "IC12") (pin "7") (pinfunction "RI4+_7") (pintype "input"))
      (node (ref "R81") (pin "1") (pinfunction "1_1") (pintype "passive"))
    )
    (net (code "145") (name "Net-(IC12-RI4-)") (class "Default")
      (node (ref "IC12") (pin "8") (pinfunction "RI4-_8") (pintype "input"))
      (node (ref "R83") (pin "2") (pinfunction "2_2") (pintype "passive"))
    )
    (net (code "146") (name "Net-(IC12-RO1)") (class "Default")
      (node (ref "IC12") (pin "15") (pinfunction "RO1_15") (pintype "output"))
      (node (ref "R92") (pin "1") (pinfunction "1_1") (pintype "passive"))
    )
    (net (code "147") (name "Net-(IC12-RO2)") (class "Default")
      (node (ref "IC12") (pin "14") (pinfunction "RO2_14") (pintype "output"))
      (node (ref "R93") (pin "1") (pinfunction "1_1") (pintype "passive"))
    )
    (net (code "148") (name "Net-(IC12-RO3)") (class "Default")
      (node (ref "IC12") (pin "11") (pinfunction "RO3_11") (pintype "output"))
      (node (ref "R127") (pin "1") (pinfunction "1_1") (pintype "passive"))
      (node (ref "R94") (pin "1") (pinfunction "1_1") (pintype "passive"))
    )
    (net (code "149") (name "Net-(IC12-RO4)") (class "Default")
      (node (ref "IC12") (pin "10") (pinfunction "RO4_10") (pintype "output"))
      (node (ref "R110") (pin "1") (pinfunction "1_1") (pintype "passive"))
    )
    (net (code "150") (name "Net-(IC12-~{EN})") (class "Default")
      (node (ref "IC12") (pin "9") (pinfunction "~{EN}_9") (pintype "input"))
      (node (ref "R85") (pin "2") (pinfunction "2_2") (pintype "passive"))
    )
    (net (code "151") (name "Net-(IC14-EN)") (class "Default")
      (node (ref "IC14") (pin "1") (pinfunction "EN_1") (pintype "input"))
      (node (ref "R90") (pin "1") (pinfunction "1_1") (pintype "passive"))
    )
    (net (code "152") (name "Net-(IC14-~{EN})") (class "Default")
      (node (ref "IC14") (pin "8") (pinfunction "~{EN}_8") (pintype "input"))
      (node (ref "R91") (pin "1") (pinfunction "1_1") (pintype "passive"))
    )
    (net (code "153") (name "P3V3D") (class "Default")
      (node (ref "IC10") (pin "15") (pinfunction "VDD_15") (pintype "power_in"))
      (node (ref "IC10") (pin "25") (pinfunction "VDD_25") (pintype "power_in"))
      (node (ref "IC10") (pin "3") (pinfunction "VDD_3") (pintype "power_in"))
      (node (ref "IC10") (pin "30") (pinfunction "VDD_30") (pintype "power_in"))
      (node (ref "IC10") (pin "8") (pinfunction "VDD_8") (pintype "power_in"))
      (node (ref "IC11") (pin "15") (pinfunction "VDD_15") (pintype "power_in"))
      (node (ref "IC11") (pin "25") (pinfunction "VDD_25") (pintype "power_in"))
      (node (ref "IC11") (pin "3") (pinfunction "VDD_3") (pintype "power_in"))
      (node (ref "IC11") (pin "30") (pinfunction "VDD_30") (pintype "power_in"))
      (node (ref "IC11") (pin "8") (pinfunction "VDD_8") (pintype "power_in"))
      (node (ref "IC12") (pin "13") (pinfunction "VCC_13") (pintype "power_in"))
      (node (ref "IC13") (pin "13") (pinfunction "VDD_13") (pintype "power_in"))
      (node (ref "IC13") (pin "8") (pinfunction "VDD_8") (pintype "power_in"))
      (node (ref "IC14") (pin "4") (pinfunction "VCC_4") (pintype "power_in"))
      (node (ref "IC16") (pin "13") (pinfunction "VDD_13") (pintype "power_in"))
      (node (ref "IC16") (pin "8") (pinfunction "VDD_8") (pintype "power_in"))
      (node (ref "IC18") (pin "13") (pinfunction "VDD_13") (pintype "power_in"))
      (node (ref "IC18") (pin "8") (pinfunction "VDD_8") (pintype "power_in"))
      (node (ref "IC2") (pin "1") (pinfunction "VCC_1") (pintype "power_in"))
      (node (ref "IC3") (pin "1") (pinfunction "VCC_1") (pintype "power_in"))
      (node (ref "IC4") (pin "4") (pinfunction "VCC_4") (pintype "power_in"))
      (node (ref "R81") (pin "2") (pinfunction "2_2") (pintype "passive"))
      (node (ref "R82") (pin "2") (pinfunction "2_2") (pintype "passive"))
      (node (ref "R84") (pin "1") (pinfunction "1_1") (pintype "passive"))
      (node (ref "R86") (pin "2") (pinfunction "2_2") (pintype "passive"))
      (node (ref "R87") (pin "2") (pinfunction "2_2") (pintype "passive"))
      (node (ref "R90") (pin "2") (pinfunction "2_2") (pintype "passive"))
      (node (ref "R95") (pin "2") (pinfunction "2_2") (pintype "passive"))
    )
    (net (code "154") (name "unconnected-(IC2-Q1-Pad6)") (class "Default")
      (node (ref "IC2") (pin "6") (pinfunction "Q1_6") (pintype "output+no_connect"))
    )
    (net (code "155") (name "unconnected-(IC2-~{Q1}-Pad5)") (class "Default")
      (node (ref "IC2") (pin "5") (pinfunction "~{Q1}_5") (pintype "output+no_connect"))
    )
    (net (code "156") (name "unconnected-(IC4-DOUT4+-Pad10)") (class "Default")
      (node (ref "IC4") (pin "10") (pinfunction "DOUT4+_10") (pintype "output+no_connect"))
    )
    (net (code "157") (name "unconnected-(IC4-DOUT4--Pad9)") (class "Default")
      (node (ref "IC4") (pin "9") (pinfunction "DOUT4-_9") (pintype "output+no_connect"))
    )
    (net (code "158") (name "unconnected-(IC10-NC-Pad17)") (class "Default")
      (node (ref "IC10") (pin "17") (pinfunction "NC_17") (pintype "passive+no_connect"))
    )
    (net (code "159") (name "unconnected-(IC11-NC-Pad17)") (class "Default")
      (node (ref "IC11") (pin "17") (pinfunction "NC_17") (pintype "passive+no_connect"))
    )
    (net (code "160") (name "unconnected-(IC13-NC-Pad7)") (class "Default")
      (node (ref "IC13") (pin "7") (pinfunction "NC_7") (pintype "passive+no_connect"))
    )
    (net (code "161") (name "unconnected-(IC13-NC-Pad16)") (class "Default")
      (node (ref "IC13") (pin "16") (pinfunction "NC_16") (pintype "passive+no_connect"))
    )
    (net (code "162") (name "unconnected-(IC13-RSV-Pad5)") (class "Default")
      (node (ref "IC13") (pin "5") (pinfunction "RSV_5") (pintype "passive+no_connect"))
    )
    (net (code "163") (name "unconnected-(IC16-NC-Pad7)") (class "Default")
      (node (ref "IC16") (pin "7") (pinfunction "NC_7") (pintype "passive+no_connect"))
    )
    (net (code "164") (name "unconnected-(IC16-NC-Pad16)") (class "Default")
      (node (ref "IC16") (pin "16") (pinfunction "NC_16") (pintype "passive+no_connect"))
    )
    (net (code "165") (name "unconnected-(IC16-RSV-Pad5)") (class "Default")
      (node (ref "IC16") (pin "5") (pinfunction "RSV_5") (pintype "passive+no_connect"))
    )
    (net (code "166") (name "unconnected-(IC18-NC-Pad7)") (class "Default")
      (node (ref "IC18") (pin "7") (pinfunction "NC_7") (pintype "passive+no_connect"))
    )
    (net (code "167") (name "unconnected-(IC18-NC-Pad16)") (class "Default")
      (node (ref "IC18") (pin "16") (pinfunction "NC_16") (pintype "passive+no_connect"))
    )
    (net (code "168") (name "unconnected-(IC18-RSV-Pad5)") (class "Default")
      (node (ref "IC18") (pin "5") (pinfunction "RSV_5") (pintype "passive+no_connect"))
    )
    (net (code "169") (name "unconnected-(R110-Pad2)") (class "Default")
      (node (ref "R110") (pin "2") (pinfunction "2_2") (pintype "passive+no_connect"))
    )
  )
)
